# lcd_buckler_mk_1_1.net
KiCad netlist of a schematic drawn in EAGLE
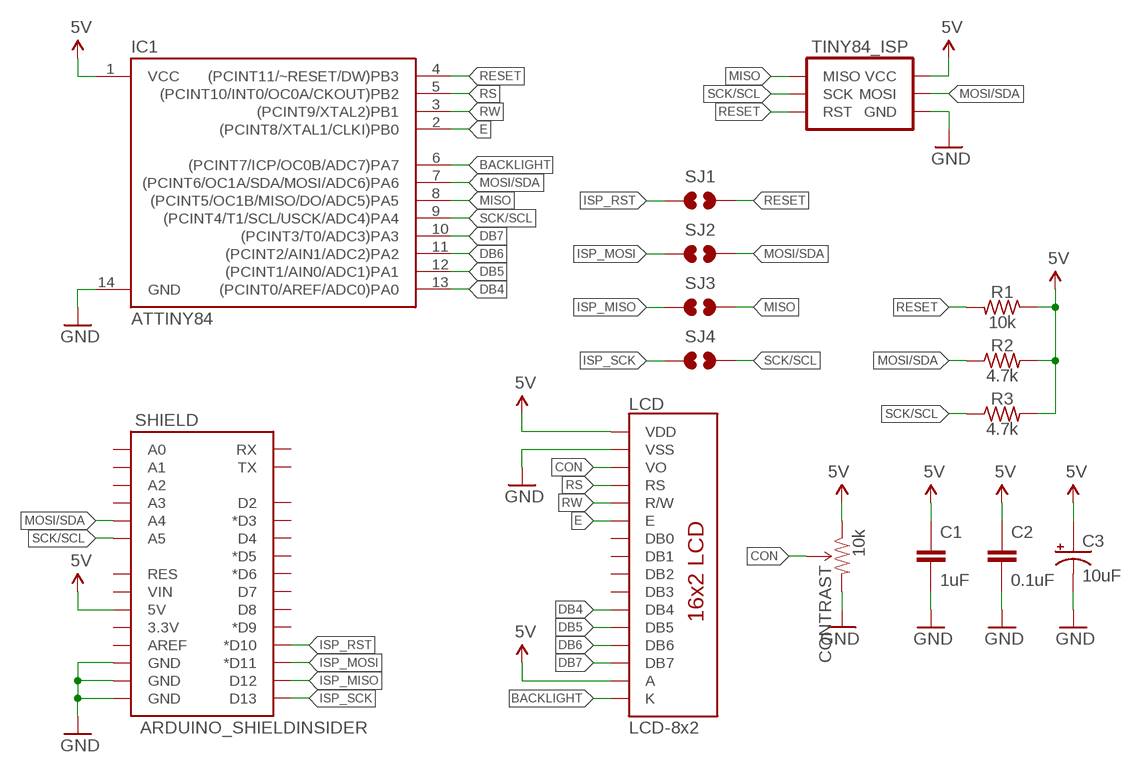
[diagram p0: schematic, sheet 1]

(export (version "E")
  (design (tool "Eeschema 10.0.6"))
  (components
    (comp (ref "C1")
      (value "1uF")
      (footprint "eagle-import:C025-024X044")
      (libsource (lib "eagle-import") (part "CAPACITOR-CERAMIC025-024X044"))
    )
    (comp (ref "C2")
      (value "0.1uF")
      (footprint "eagle-import:C025-024X044")
      (libsource (lib "eagle-import") (part "CAPACITOR-CERAMIC025-024X044"))
    )
    (comp (ref "C3")
      (value "10uF")
      (footprint "eagle-import:E2,5-5")
      (libsource (lib "eagle-import") (part "CAPACITOR-POLARIZEDE2.5-5"))
    )
    (comp (ref "CONTRAST")
      (value "10k")
      (footprint "eagle-import:TRIM_POT_PTH")
      (libsource (lib "eagle-import") (part "TRIMPOTPTH"))
    )
    (comp (ref "IC1")
      (value "ATTINY84")
      (footprint "eagle-import:DIL14")
      (libsource (lib "eagle-import") (part "ATTINY84ATTINY84-20PU"))
    )
    (comp (ref "LCD")
      (value "LCD-8x2")
      (footprint "eagle-import:LCD-8X2")
      (libsource (lib "eagle-import") (part "LCD-16X28X2"))
    )
    (comp (ref "R1")
      (value "10k")
      (footprint "eagle-import:RESISTOR-AXIAL-PTH-7.62MM")
      (libsource (lib "eagle-import") (part "RESISTORPTH-AXIAL-7.62MM"))
    )
    (comp (ref "R2")
      (value "4.7k")
      (footprint "eagle-import:RESISTOR-AXIAL-PTH-7.62MM")
      (libsource (lib "eagle-import") (part "RESISTORPTH-AXIAL-7.62MM"))
    )
    (comp (ref "R3")
      (value "4.7k")
      (footprint "eagle-import:RESISTOR-AXIAL-PTH-7.62MM")
      (libsource (lib "eagle-import") (part "RESISTORPTH-AXIAL-7.62MM"))
    )
    (comp (ref "SHIELD")
      (value "ARDUINO_SHIELDINSIDER")
      (footprint "eagle-import:ARDUINO_SHIELD_NOOUTLINE_INSIDE")
      (libsource (lib "eagle-import") (part "ARDUINO_SHIELDINSIDER"))
    )
    (comp (ref "SJ1")
      (value "JUMPER-PAD-2-NO")
      (footprint "eagle-import:PAD-JUMPER-2-NO_NO_SILK")
      (libsource (lib "eagle-import") (part "JUMPER-PAD-2-NO"))
    )
    (comp (ref "SJ2")
      (value "JUMPER-PAD-2-NO")
      (footprint "eagle-import:PAD-JUMPER-2-NO_NO_SILK")
      (libsource (lib "eagle-import") (part "JUMPER-PAD-2-NO"))
    )
    (comp (ref "SJ3")
      (value "JUMPER-PAD-2-NO")
      (footprint "eagle-import:PAD-JUMPER-2-NO_NO_SILK")
      (libsource (lib "eagle-import") (part "JUMPER-PAD-2-NO"))
    )
    (comp (ref "SJ4")
      (value "JUMPER-PAD-2-NO")
      (footprint "eagle-import:PAD-JUMPER-2-NO_NO_SILK")
      (libsource (lib "eagle-import") (part "JUMPER-PAD-2-NO"))
    )
    (comp (ref "TINY84_ISP")
      (value "AVR_SPI_PRG_6PTH")
      (footprint "eagle-import:2X3")
      (libsource (lib "eagle-import") (part "AVR_SPI_PRG_6PTH"))
    )
  )
  (nets
    (net (code "1") (name "5V") (class "Default")
      (node (ref "C1") (pin "1") (pinfunction "1_1") (pintype "passive"))
      (node (ref "C2") (pin "1") (pinfunction "1_1") (pintype "passive"))
      (node (ref "C3") (pin "+") (pinfunction "+_+") (pintype "passive"))
      (node (ref "CONTRAST") (pin "1") (pinfunction "CCW_1") (pintype "passive"))
      (node (ref "IC1") (pin "1") (pinfunction "VCC_1") (pintype "bidirectional"))
      (node (ref "LCD") (pin "15") (pinfunction "A_15") (pintype "power_in"))
      (node (ref "LCD") (pin "2") (pinfunction "VDD_2") (pintype "power_in"))
      (node (ref "R1") (pin "P$1") (pinfunction "1_P$1") (pintype "passive"))
      (node (ref "R2") (pin "P$2") (pinfunction "2_P$2") (pintype "passive"))
      (node (ref "R3") (pin "P$2") (pinfunction "2_P$2") (pintype "passive"))
      (node (ref "SHIELD") (pin "5V") (pinfunction "5V_5V") (pintype "bidirectional"))
      (node (ref "TINY84_ISP") (pin "2") (pinfunction "VCC_2") (pintype "passive"))
    )
    (net (code "2") (name "BACKLIGHT") (class "Default")
      (node (ref "IC1") (pin "6") (pinfunction "(PCINT7/ICP/OC0B/ADC7)PA7_6") (pintype "bidirectional"))
      (node (ref "LCD") (pin "16") (pinfunction "K_16") (pintype "power_in"))
    )
    (net (code "3") (name "CON") (class "Default")
      (node (ref "CONTRAST") (pin "2") (pinfunction "WIPER_2") (pintype "passive"))
      (node (ref "LCD") (pin "3") (pinfunction "VO_3") (pintype "bidirectional"))
    )
    (net (code "4") (name "DB4") (class "Default")
      (node (ref "IC1") (pin "13") (pinfunction "(PCINT0/AREF/ADC0)PA0_13") (pintype "bidirectional"))
      (node (ref "LCD") (pin "11") (pinfunction "DB4_11") (pintype "bidirectional"))
    )
    (net (code "5") (name "DB5") (class "Default")
      (node (ref "IC1") (pin "12") (pinfunction "(PCINT1/AIN0/ADC1)PA1_12") (pintype "bidirectional"))
      (node (ref "LCD") (pin "12") (pinfunction "DB5_12") (pintype "bidirectional"))
    )
    (net (code "6") (name "DB6") (class "Default")
      (node (ref "IC1") (pin "11") (pinfunction "(PCINT2/AIN1/ADC2)PA2_11") (pintype "bidirectional"))
      (node (ref "LCD") (pin "13") (pinfunction "DB6_13") (pintype "bidirectional"))
    )
    (net (code "7") (name "DB7") (class "Default")
      (node (ref "IC1") (pin "10") (pinfunction "(PCINT3/T0/ADC3)PA3_10") (pintype "bidirectional"))
      (node (ref "LCD") (pin "14") (pinfunction "DB7_14") (pintype "bidirectional"))
    )
    (net (code "8") (name "E") (class "Default")
      (node (ref "IC1") (pin "2") (pinfunction "(PCINT8/XTAL1/CLKI)PB0_2") (pintype "bidirectional"))
      (node (ref "LCD") (pin "6") (pinfunction "E_6") (pintype "input"))
    )
    (net (code "9") (name "GND") (class "Default")
      (node (ref "C1") (pin "2") (pinfunction "2_2") (pintype "passive"))
      (node (ref "C2") (pin "2") (pinfunction "2_2") (pintype "passive"))
      (node (ref "C3") (pin "-") (pinfunction "-_-") (pintype "passive"))
      (node (ref "CONTRAST") (pin "3") (pinfunction "CW_3") (pintype "passive"))
      (node (ref "IC1") (pin "14") (pinfunction "GND_14") (pintype "bidirectional"))
      (node (ref "LCD") (pin "1") (pinfunction "VSS_1") (pintype "power_in"))
      (node (ref "SHIELD") (pin "GND@0") (pinfunction "GND_GND@0") (pintype "bidirectional"))
      (node (ref "SHIELD") (pin "GND@1") (pinfunction "GND_GND@1") (pintype "bidirectional"))
      (node (ref "SHIELD") (pin "GND@2") (pinfunction "GND_GND@2") (pintype "bidirectional"))
      (node (ref "TINY84_ISP") (pin "6") (pinfunction "GND_6") (pintype "passive"))
    )
    (net (code "10") (name "ISP_MISO") (class "Default")
      (node (ref "SHIELD") (pin "D12") (pinfunction "D12_D12") (pintype "bidirectional"))
      (node (ref "SJ3") (pin "1") (pinfunction "1_1") (pintype "passive"))
    )
    (net (code "11") (name "ISP_MOSI") (class "Default")
      (node (ref "SHIELD") (pin "D11") (pinfunction "*D11_D11") (pintype "bidirectional"))
      (node (ref "SJ2") (pin "1") (pinfunction "1_1") (pintype "passive"))
    )
    (net (code "12") (name "ISP_RST") (class "Default")
      (node (ref "SHIELD") (pin "D10") (pinfunction "*D10_D10") (pintype "bidirectional"))
      (node (ref "SJ1") (pin "1") (pinfunction "1_1") (pintype "passive"))
    )
    (net (code "13") (name "ISP_SCK") (class "Default")
      (node (ref "SHIELD") (pin "D13") (pinfunction "D13_D13") (pintype "bidirectional"))
      (node (ref "SJ4") (pin "1") (pinfunction "1_1") (pintype "passive"))
    )
    (net (code "14") (name "MISO") (class "Default")
      (node (ref "IC1") (pin "8") (pinfunction "(PCINT5/OC1B/MISO/DO/ADC5)PA5_8") (pintype "bidirectional"))
      (node (ref "SJ3") (pin "2") (pinfunction "2_2") (pintype "passive"))
      (node (ref "TINY84_ISP") (pin "1") (pinfunction "MISO_1") (pintype "passive"))
    )
    (net (code "15") (name "MOSI{slash}SDA") (class "Default")
      (node (ref "IC1") (pin "7") (pinfunction "(PCINT6/OC1A/SDA/MOSI/ADC6)PA6_7") (pintype "bidirectional"))
      (node (ref "R2") (pin "P$1") (pinfunction "1_P$1") (pintype "passive"))
      (node (ref "SHIELD") (pin "A4") (pinfunction "A4_A4") (pintype "bidirectional"))
      (node (ref "SJ2") (pin "2") (pinfunction "2_2") (pintype "passive"))
      (node (ref "TINY84_ISP") (pin "4") (pinfunction "MOSI_4") (pintype "passive"))
    )
    (net (code "16") (name "RESET") (class "Default")
      (node (ref "IC1") (pin "4") (pinfunction "(PCINT11/~{RESET/DW})PB3_4") (pintype "bidirectional"))
      (node (ref "R1") (pin "P$2") (pinfunction "2_P$2") (pintype "passive"))
      (node (ref "SJ1") (pin "2") (pinfunction "2_2") (pintype "passive"))
      (node (ref "TINY84_ISP") (pin "5") (pinfunction "RST_5") (pintype "passive"))
    )
    (net (code "17") (name "RS") (class "Default")
      (node (ref "IC1") (pin "5") (pinfunction "(PCINT10/INT0/OC0A/CKOUT)PB2_5") (pintype "bidirectional"))
      (node (ref "LCD") (pin "4") (pinfunction "RS_4") (pintype "input"))
    )
    (net (code "18") (name "RW") (class "Default")
      (node (ref "IC1") (pin "3") (pinfunction "(PCINT9/XTAL2)PB1_3") (pintype "bidirectional"))
      (node (ref "LCD") (pin "5") (pinfunction "R/W_5") (pintype "input"))
    )
    (net (code "19") (name "SCK{slash}SCL") (class "Default")
      (node (ref "IC1") (pin "9") (pinfunction "(PCINT4/T1/SCL/USCK/ADC4)PA4_9") (pintype "bidirectional"))
      (node (ref "R3") (pin "P$1") (pinfunction "1_P$1") (pintype "passive"))
      (node (ref "SHIELD") (pin "A5") (pinfunction "A5_A5") (pintype "bidirectional"))
      (node (ref "SJ4") (pin "2") (pinfunction "2_2") (pintype "passive"))
      (node (ref "TINY84_ISP") (pin "3") (pinfunction "SCK_3") (pintype "passive"))
    )
    (net (code "20") (name "unconnected-(LCD-DB0-Pad7)") (class "Default")
      (node (ref "LCD") (pin "7") (pinfunction "DB0_7") (pintype "bidirectional"))
    )
    (net (code "21") (name "unconnected-(LCD-DB1-Pad8)") (class "Default")
      (node (ref "LCD") (pin "8") (pinfunction "DB1_8") (pintype "bidirectional"))
    )
    (net (code "22") (name "unconnected-(LCD-DB2-Pad9)") (class "Default")
      (node (ref "LCD") (pin "9") (pinfunction "DB2_9") (pintype "bidirectional"))
    )
    (net (code "23") (name "unconnected-(LCD-DB3-Pad10)") (class "Default")
      (node (ref "LCD") (pin "10") (pinfunction "DB3_10") (pintype "bidirectional"))
    )
    (net (code "24") (name "unconnected-(SHIELD-*D3-PadD3)") (class "Default")
      (node (ref "SHIELD") (pin "D3") (pinfunction "*D3_D3") (pintype "bidirectional"))
    )
    (net (code "25") (name "unconnected-(SHIELD-*D5-PadD5)") (class "Default")
      (node (ref "SHIELD") (pin "D5") (pinfunction "*D5_D5") (pintype "bidirectional"))
    )
    (net (code "26") (name "unconnected-(SHIELD-*D6-PadD6)") (class "Default")
      (node (ref "SHIELD") (pin "D6") (pinfunction "*D6_D6") (pintype "bidirectional"))
    )
    (net (code "27") (name "unconnected-(SHIELD-*D9-PadD9)") (class "Default")
      (node (ref "SHIELD") (pin "D9") (pinfunction "*D9_D9") (pintype "bidirectional"))
    )
    (net (code "28") (name "unconnected-(SHIELD-Pad3.3V)") (class "Default")
      (node (ref "SHIELD") (pin "3.3V") (pinfunction "3.3V_3.3V") (pintype "bidirectional"))
    )
    (net (code "29") (name "unconnected-(SHIELD-PadA0)") (class "Default")
      (node (ref "SHIELD") (pin "A0") (pinfunction "A0_A0") (pintype "bidirectional"))
    )
    (net (code "30") (name "unconnected-(SHIELD-PadA1)") (class "Default")
      (node (ref "SHIELD") (pin "A1") (pinfunction "A1_A1") (pintype "bidirectional"))
    )
    (net (code "31") (name "unconnected-(SHIELD-PadA2)") (class "Default")
      (node (ref "SHIELD") (pin "A2") (pinfunction "A2_A2") (pintype "bidirectional"))
    )
    (net (code "32") (name "unconnected-(SHIELD-PadA3)") (class "Default")
      (node (ref "SHIELD") (pin "A3") (pinfunction "A3_A3") (pintype "bidirectional"))
    )
    (net (code "33") (name "unconnected-(SHIELD-PadAREF)") (class "Default")
      (node (ref "SHIELD") (pin "AREF") (pinfunction "AREF_AREF") (pintype "bidirectional"))
    )
    (net (code "34") (name "unconnected-(SHIELD-PadD2)") (class "Default")
      (node (ref "SHIELD") (pin "D2") (pinfunction "D2_D2") (pintype "bidirectional"))
    )
    (net (code "35") (name "unconnected-(SHIELD-PadD4)") (class "Default")
      (node (ref "SHIELD") (pin "D4") (pinfunction "D4_D4") (pintype "bidirectional"))
    )
    (net (code "36") (name "unconnected-(SHIELD-PadD7)") (class "Default")
      (node (ref "SHIELD") (pin "D7") (pinfunction "D7_D7") (pintype "bidirectional"))
    )
    (net (code "37") (name "unconnected-(SHIELD-PadD8)") (class "Default")
      (node (ref "SHIELD") (pin "D8") (pinfunction "D8_D8") (pintype "bidirectional"))
    )
    (net (code "38") (name "unconnected-(SHIELD-PadRES)") (class "Default")
      (node (ref "SHIELD") (pin "RES") (pinfunction "RES_RES") (pintype "bidirectional"))
    )
    (net (code "39") (name "unconnected-(SHIELD-PadRX)") (class "Default")
      (node (ref "SHIELD") (pin "RX") (pinfunction "RX_RX") (pintype "bidirectional"))
    )
    (net (code "40") (name "unconnected-(SHIELD-PadTX)") (class "Default")
      (node (ref "SHIELD") (pin "TX") (pinfunction "TX_TX") (pintype "bidirectional"))
    )
    (net (code "41") (name "unconnected-(SHIELD-PadVIN)") (class "Default")
      (node (ref "SHIELD") (pin "VIN") (pinfunction "VIN_VIN") (pintype "bidirectional"))
    )
  )
)
